# minibotfinal.net
KiCad netlist of a schematic drawn in EAGLE
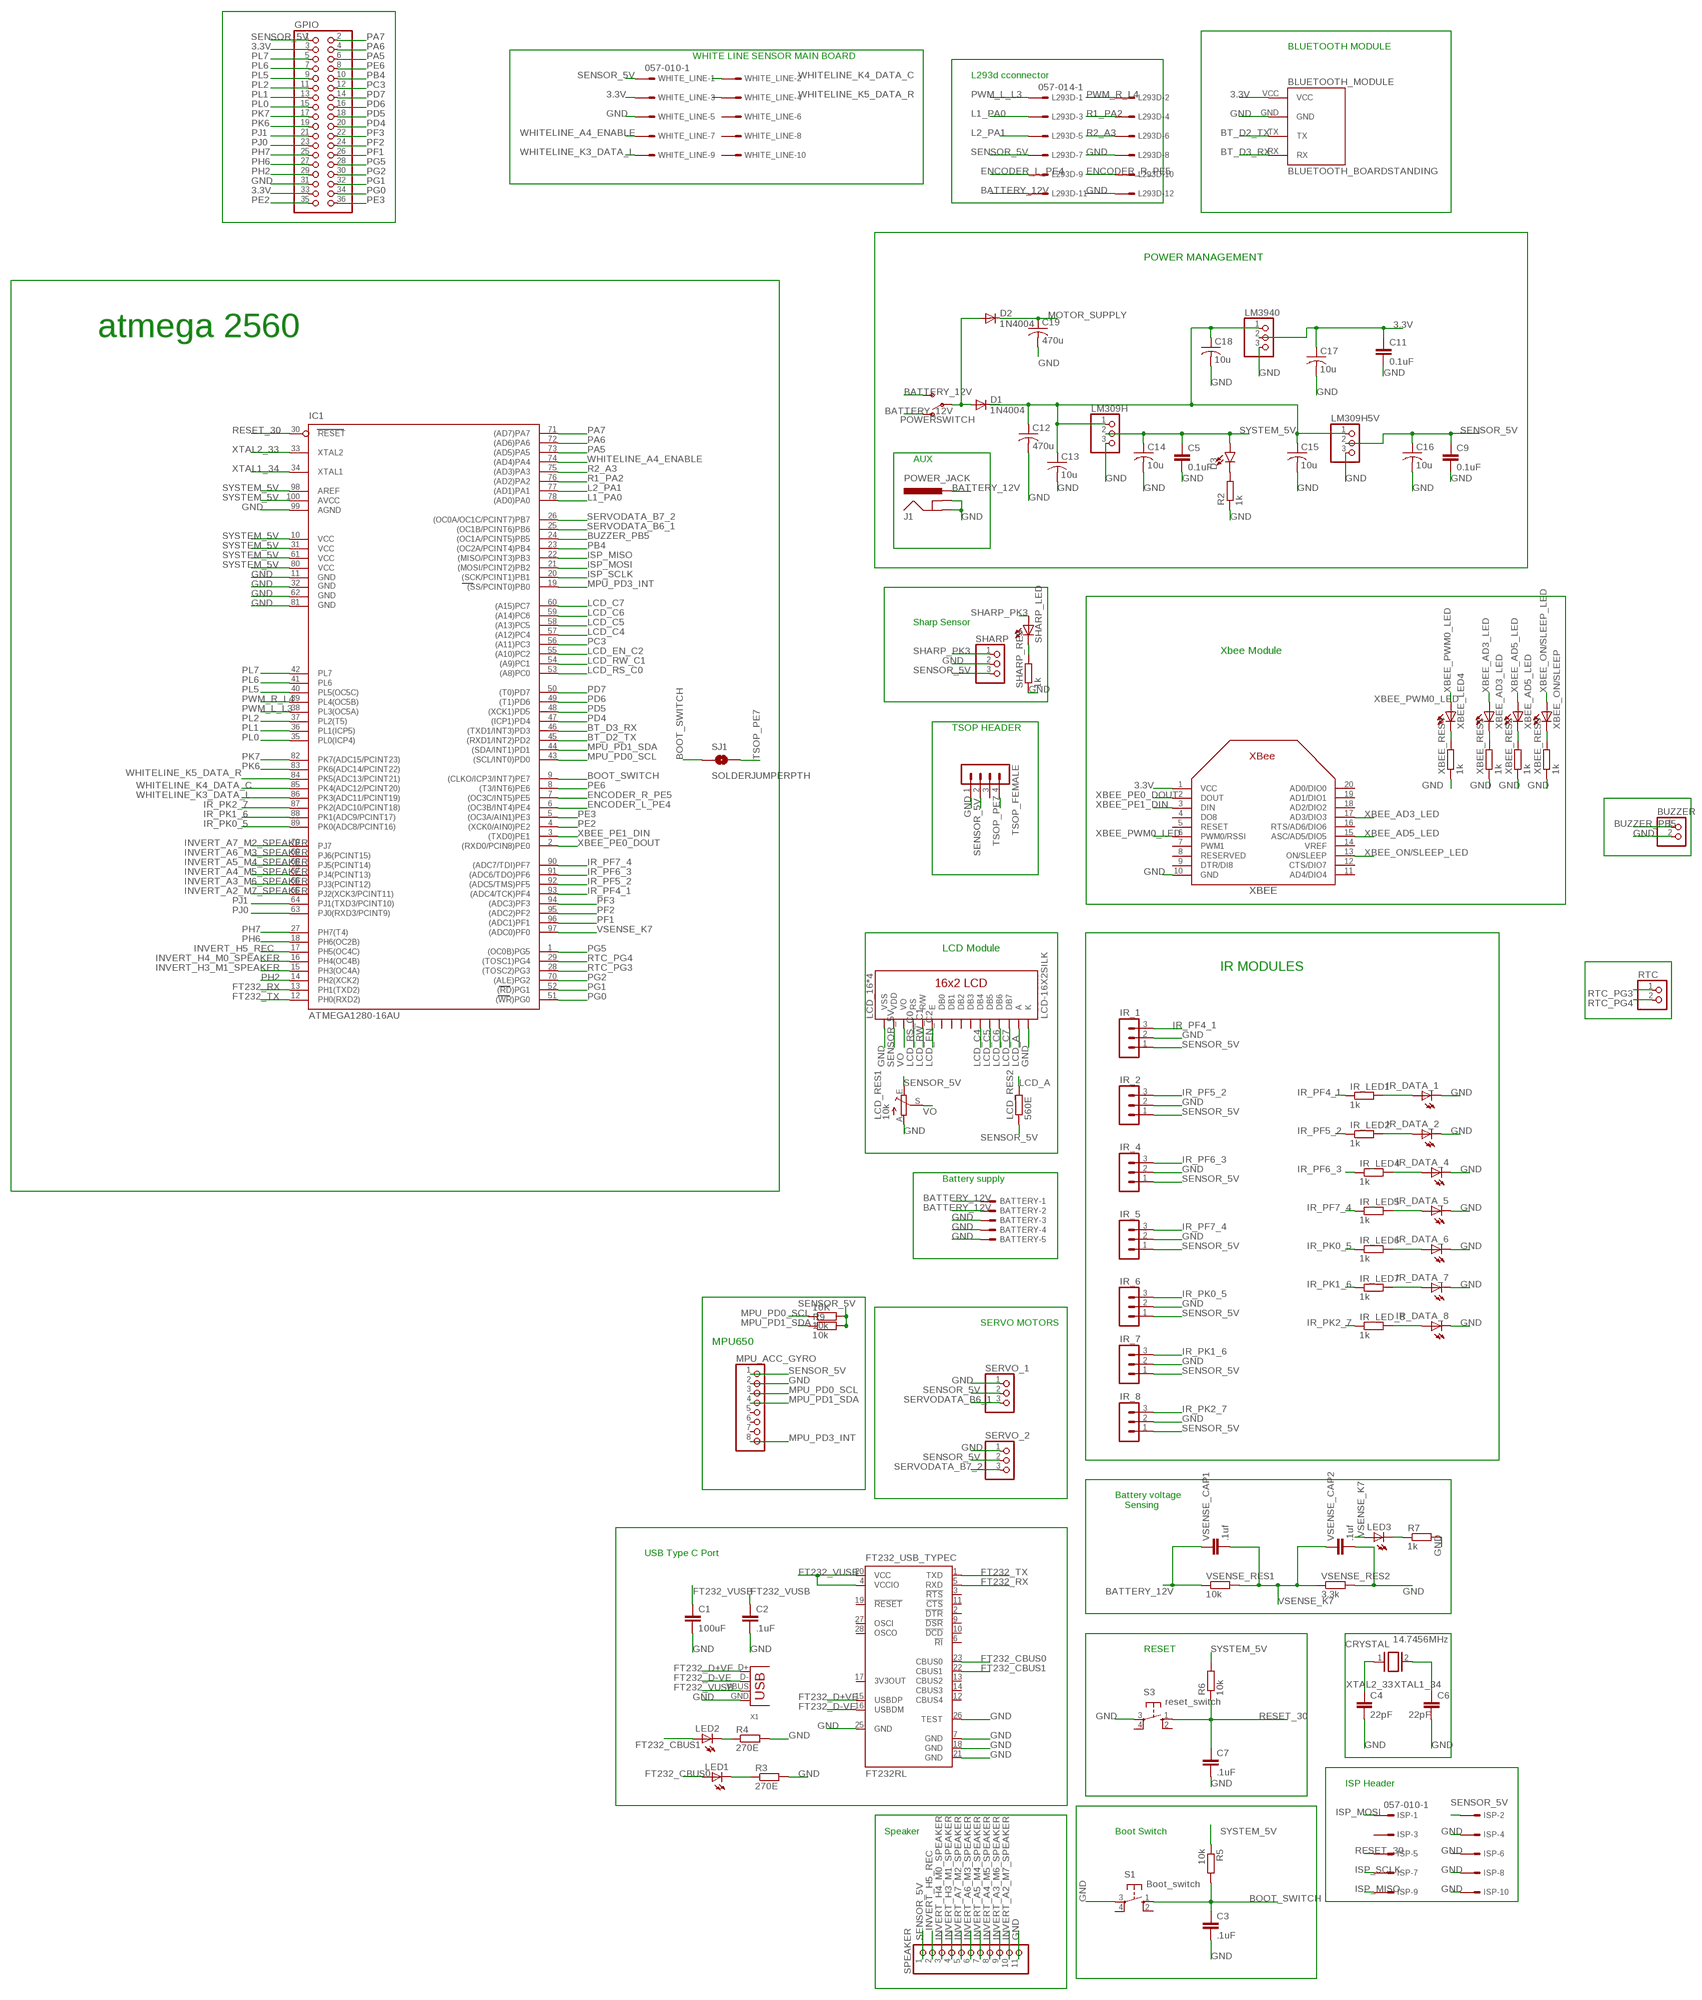
[diagram p0: schematic, sheet 1]

(export (version "E")
  (design (tool "Eeschema 10.0.6"))
  (components
    (comp (ref "10K")
      (value "10k")
      (footprint "eagle-import:R1206")
      (libsource (lib "eagle-import") (part "R-EU_R1206"))
    )
    (comp (ref "BATTERY")
      (value "KK-156-5")
      (footprint "eagle-import:KK-156-5")
      (libsource (lib "eagle-import") (part "KK-156-5"))
    )
    (comp (ref "BLUETOOTH_MODULE")
      (value "BLUETOOTH_BOARDSTANDING")
      (footprint "eagle-import:BT_BOARD_FOOTPRINT_STANDING")
      (libsource (lib "eagle-import") (part "BLUETOOTH_BOARDSTANDING"))
    )
    (comp (ref "BUZZER")
      (value "PINHD-1X2")
      (footprint "eagle-import:1X02")
      (libsource (lib "eagle-import") (part "PINHD-1X2"))
    )
    (comp (ref "C1")
      (value "100uF")
      (footprint "eagle-import:C1206")
      (libsource (lib "eagle-import") (part "C-EUC1206"))
    )
    (comp (ref "C2")
      (value ".1uF")
      (footprint "eagle-import:C1206")
      (libsource (lib "eagle-import") (part "C-EUC1206"))
    )
    (comp (ref "C3")
      (value ".1uF")
      (footprint "eagle-import:C1206")
      (libsource (lib "eagle-import") (part "C-EUC1206"))
    )
    (comp (ref "C4")
      (value "22pF")
      (footprint "eagle-import:C1206")
      (libsource (lib "eagle-import") (part "C-EUC1206"))
    )
    (comp (ref "C5")
      (value "0.1uF")
      (footprint "eagle-import:C1206")
      (libsource (lib "eagle-import") (part "C-EUC1206"))
    )
    (comp (ref "C6")
      (value "22pF")
      (footprint "eagle-import:C1206")
      (libsource (lib "eagle-import") (part "C-EUC1206"))
    )
    (comp (ref "C7")
      (value ".1uF")
      (footprint "eagle-import:C1206")
      (libsource (lib "eagle-import") (part "C-EUC1206"))
    )
    (comp (ref "C9")
      (value "0.1uF")
      (footprint "eagle-import:C1206")
      (libsource (lib "eagle-import") (part "C-EUC1206"))
    )
    (comp (ref "C11")
      (value "0.1uF")
      (footprint "eagle-import:C1206")
      (libsource (lib "eagle-import") (part "C-EUC1206"))
    )
    (comp (ref "C12")
      (value "470u")
      (footprint "eagle-import:C025-050X050")
      (libsource (lib "eagle-import") (part "C-US025-050X050"))
    )
    (comp (ref "C13")
      (value "10u")
      (footprint "eagle-import:C025-050X050")
      (libsource (lib "eagle-import") (part "C-US025-050X050"))
    )
    (comp (ref "C14")
      (value "10u")
      (footprint "eagle-import:C025-050X050")
      (libsource (lib "eagle-import") (part "C-US025-050X050"))
    )
    (comp (ref "C15")
      (value "10u")
      (footprint "eagle-import:C025-050X050")
      (libsource (lib "eagle-import") (part "C-US025-050X050"))
    )
    (comp (ref "C16")
      (value "10u")
      (footprint "eagle-import:C025-050X050")
      (libsource (lib "eagle-import") (part "C-US025-050X050"))
    )
    (comp (ref "C17")
      (value "10u")
      (footprint "eagle-import:C025-050X050")
      (libsource (lib "eagle-import") (part "C-US025-050X050"))
    )
    (comp (ref "C18")
      (value "10u")
      (footprint "eagle-import:C025-050X050")
      (libsource (lib "eagle-import") (part "C-US025-050X050"))
    )
    (comp (ref "C19")
      (value "470u")
      (footprint "eagle-import:C025-050X050")
      (libsource (lib "eagle-import") (part "C-US025-050X050"))
    )
    (comp (ref "CRYSTAL")
      (value "14.7456MHz")
      (footprint "eagle-import:QS")
      (libsource (lib "eagle-import") (part "XTAL/S"))
    )
    (comp (ref "D1")
      (value "1N4004")
      (footprint "eagle-import:DO41-10")
      (libsource (lib "eagle-import") (part "1N4004"))
    )
    (comp (ref "D2")
      (value "1N4004")
      (footprint "eagle-import:DO41-10")
      (libsource (lib "eagle-import") (part "1N4004"))
    )
    (comp (ref "D3")
      (value "LED1206")
      (footprint "eagle-import:LED-1206")
      (libsource (lib "eagle-import") (part "LED1206"))
    )
    (comp (ref "FT232_USB_TYPEC")
      (value "FT232RL")
      (footprint "eagle-import:SSOP28")
      (libsource (lib "eagle-import") (part "FT232RL"))
    )
    (comp (ref "GPIO")
      (value "PINHD-2X18")
      (footprint "eagle-import:2X18")
      (libsource (lib "eagle-import") (part "PINHD-2X18"))
    )
    (comp (ref "IC1")
      (value "ATMEGA1280-16AU")
      (footprint "eagle-import:TQFP100")
      (libsource (lib "eagle-import") (part "ATMEGAAU1280-16"))
    )
    (comp (ref "IR_1")
      (value "MA03-1")
      (footprint "eagle-import:MA03-1")
      (libsource (lib "eagle-import") (part "MA03-1"))
    )
    (comp (ref "IR_2")
      (value "MA03-1")
      (footprint "eagle-import:MA03-1")
      (libsource (lib "eagle-import") (part "MA03-1"))
    )
    (comp (ref "IR_4")
      (value "MA03-1")
      (footprint "eagle-import:MA03-1")
      (libsource (lib "eagle-import") (part "MA03-1"))
    )
    (comp (ref "IR_5")
      (value "MA03-1")
      (footprint "eagle-import:MA03-1")
      (libsource (lib "eagle-import") (part "MA03-1"))
    )
    (comp (ref "IR_6")
      (value "MA03-1")
      (footprint "eagle-import:MA03-1")
      (libsource (lib "eagle-import") (part "MA03-1"))
    )
    (comp (ref "IR_7")
      (value "MA03-1")
      (footprint "eagle-import:MA03-1")
      (libsource (lib "eagle-import") (part "MA03-1"))
    )
    (comp (ref "IR_8")
      (value "MA03-1")
      (footprint "eagle-import:MA03-1")
      (libsource (lib "eagle-import") (part "MA03-1"))
    )
    (comp (ref "IR_DATA_1")
      (value "LEDSMT1206")
      (footprint "eagle-import:1206")
      (libsource (lib "eagle-import") (part "LEDSMT1206"))
    )
    (comp (ref "IR_DATA_2")
      (value "LEDSMT1206")
      (footprint "eagle-import:1206")
      (libsource (lib "eagle-import") (part "LEDSMT1206"))
    )
    (comp (ref "IR_DATA_4")
      (value "LEDSMT1206")
      (footprint "eagle-import:1206")
      (libsource (lib "eagle-import") (part "LEDSMT1206"))
    )
    (comp (ref "IR_DATA_5")
      (value "LEDSMT1206")
      (footprint "eagle-import:1206")
      (libsource (lib "eagle-import") (part "LEDSMT1206"))
    )
    (comp (ref "IR_DATA_6")
      (value "LEDSMT1206")
      (footprint "eagle-import:1206")
      (libsource (lib "eagle-import") (part "LEDSMT1206"))
    )
    (comp (ref "IR_DATA_7")
      (value "LEDSMT1206")
      (footprint "eagle-import:1206")
      (libsource (lib "eagle-import") (part "LEDSMT1206"))
    )
    (comp (ref "IR_DATA_8")
      (value "LEDSMT1206")
      (footprint "eagle-import:1206")
      (libsource (lib "eagle-import") (part "LEDSMT1206"))
    )
    (comp (ref "IR_LED1")
      (value "1k")
      (footprint "eagle-import:R1206")
      (libsource (lib "eagle-import") (part "R-EU_R1206"))
    )
    (comp (ref "IR_LED2")
      (value "1k")
      (footprint "eagle-import:R1206")
      (libsource (lib "eagle-import") (part "R-EU_R1206"))
    )
    (comp (ref "IR_LED4")
      (value "1k")
      (footprint "eagle-import:R1206")
      (libsource (lib "eagle-import") (part "R-EU_R1206"))
    )
    (comp (ref "IR_LED5")
      (value "1k")
      (footprint "eagle-import:R1206")
      (libsource (lib "eagle-import") (part "R-EU_R1206"))
    )
    (comp (ref "IR_LED6")
      (value "1k")
      (footprint "eagle-import:R1206")
      (libsource (lib "eagle-import") (part "R-EU_R1206"))
    )
    (comp (ref "IR_LED7")
      (value "1k")
      (footprint "eagle-import:R1206")
      (libsource (lib "eagle-import") (part "R-EU_R1206"))
    )
    (comp (ref "IR_LED_8")
      (value "1k")
      (footprint "eagle-import:R1206")
      (libsource (lib "eagle-import") (part "R-EU_R1206"))
    )
    (comp (ref "ISP")
      (value "057-010-1")
      (footprint "eagle-import:057-010-1")
      (libsource (lib "eagle-import") (part "057-010-1"))
    )
    (comp (ref "J1")
      (value "POWER_JACK")
      (footprint "eagle-import:POWER_JACK_PTH")
      (libsource (lib "eagle-import") (part "POWER_JACK"))
    )
    (comp (ref "L293D")
      (value "057-014-1")
      (footprint "eagle-import:057-014-1")
      (libsource (lib "eagle-import") (part "057-014-1"))
    )
    (comp (ref "LCD_16*4")
      (value "LCD-16X2SILK")
      (footprint "eagle-import:LCD-16X2")
      (libsource (lib "eagle-import") (part "LCD-16X2SILK"))
    )
    (comp (ref "LCD_RES1")
      (value "10k")
      (footprint "eagle-import:CA6V")
      (libsource (lib "eagle-import") (part "TRIM_EU-CA6V"))
    )
    (comp (ref "LCD_RES2")
      (value "560E")
      (footprint "eagle-import:R1206")
      (libsource (lib "eagle-import") (part "R-EU_R1206"))
    )
    (comp (ref "LED1")
      (value "LEDSMT1206")
      (footprint "eagle-import:1206")
      (libsource (lib "eagle-import") (part "LEDSMT1206"))
    )
    (comp (ref "LED2")
      (value "LEDSMT1206")
      (footprint "eagle-import:1206")
      (libsource (lib "eagle-import") (part "LEDSMT1206"))
    )
    (comp (ref "LED3")
      (value "LEDSMT1206")
      (footprint "eagle-import:1206")
      (libsource (lib "eagle-import") (part "LEDSMT1206"))
    )
    (comp (ref "LM309H")
      (value "PINHD-1X3")
      (footprint "eagle-import:1X03")
      (libsource (lib "eagle-import") (part "PINHD-1X3"))
    )
    (comp (ref "LM309H5V")
      (value "PINHD-1X3")
      (footprint "eagle-import:1X03")
      (libsource (lib "eagle-import") (part "PINHD-1X3"))
    )
    (comp (ref "LM3940")
      (value "PINHD-1X3")
      (footprint "eagle-import:1X03")
      (libsource (lib "eagle-import") (part "PINHD-1X3"))
    )
    (comp (ref "MPU_ACC_GYRO")
      (value "PINHD-1X8")
      (footprint "eagle-import:1X08")
      (libsource (lib "eagle-import") (part "PINHD-1X8"))
    )
    (comp (ref "POWERSWITCH")
      (value "SWITCH-SPDT-PTH-11.6X4.0MM-LOCK")
      (footprint "eagle-import:SWITCH_SPDT_PTH_11.6X4.0MM_LOCK")
      (libsource (lib "eagle-import") (part "SWITCH-SPDT-PTH-11.6X4.0MM-LOCK"))
    )
    (comp (ref "R2")
      (value "1k")
      (footprint "eagle-import:R1206")
      (libsource (lib "eagle-import") (part "R-EU_R1206"))
    )
    (comp (ref "R3")
      (value "270E")
      (footprint "eagle-import:R1206")
      (libsource (lib "eagle-import") (part "R-EU_R1206"))
    )
    (comp (ref "R4")
      (value "270E")
      (footprint "eagle-import:R1206")
      (libsource (lib "eagle-import") (part "R-EU_R1206"))
    )
    (comp (ref "R5")
      (value "10k")
      (footprint "eagle-import:R1206")
      (libsource (lib "eagle-import") (part "R-EU_R1206"))
    )
    (comp (ref "R6")
      (value "10k")
      (footprint "eagle-import:R1206")
      (libsource (lib "eagle-import") (part "R-EU_R1206"))
    )
    (comp (ref "R7")
      (value "1k")
      (footprint "eagle-import:R1206")
      (libsource (lib "eagle-import") (part "R-EU_R1206"))
    )
    (comp (ref "R9")
      (value "10k")
      (footprint "eagle-import:R1206")
      (libsource (lib "eagle-import") (part "R-EU_R1206"))
    )
    (comp (ref "RTC")
      (value "PINHD-1X2")
      (footprint "eagle-import:1X02")
      (libsource (lib "eagle-import") (part "PINHD-1X2"))
    )
    (comp (ref "S1")
      (value "Boot_switch")
      (footprint "eagle-import:B3F-10XX")
      (fields (field (name "MPN") "B3F-1000"))
      (libsource (lib "eagle-import") (part "10-XX"))
    )
    (comp (ref "S3")
      (value "reset_switch")
      (footprint "eagle-import:B3F-10XX")
      (fields (field (name "MPN") "B3F-1000"))
      (libsource (lib "eagle-import") (part "10-XX"))
    )
    (comp (ref "SERVO_1")
      (value "PINHD-1X3")
      (footprint "eagle-import:1X03")
      (libsource (lib "eagle-import") (part "pinhead_325_PINHD-1X3"))
    )
    (comp (ref "SERVO_2")
      (value "PINHD-1X3")
      (footprint "eagle-import:1X03")
      (libsource (lib "eagle-import") (part "pinhead_325_PINHD-1X3"))
    )
    (comp (ref "SHARP")
      (value "PINHD-1X3")
      (footprint "eagle-import:1X03")
      (libsource (lib "eagle-import") (part "pinhead_325_PINHD-1X3"))
    )
    (comp (ref "SHARP_LED")
      (value "LEDSMT1206")
      (footprint "eagle-import:1206")
      (libsource (lib "eagle-import") (part "LEDSMT1206"))
    )
    (comp (ref "SHARP_RES")
      (value "1k")
      (footprint "eagle-import:R1206")
      (libsource (lib "eagle-import") (part "R-EU_R1206"))
    )
    (comp (ref "SJ1")
      (value "SOLDERJUMPERPTH")
      (footprint "eagle-import:SJ_2S-PTH")
      (libsource (lib "eagle-import") (part "SOLDERJUMPERPTH"))
    )
    (comp (ref "SPEAKER")
      (value "PINHD-1X11")
      (footprint "eagle-import:1X11")
      (libsource (lib "eagle-import") (part "PINHD-1X11"))
    )
    (comp (ref "TSOP_FEMALE")
      (value "MA04-1")
      (footprint "eagle-import:MA04-1")
      (libsource (lib "eagle-import") (part "MA04-1"))
    )
    (comp (ref "VSENSE_CAP1")
      (value ".1uf")
      (footprint "eagle-import:C1206")
      (libsource (lib "eagle-import") (part "C-EUC1206"))
    )
    (comp (ref "VSENSE_CAP2")
      (value ".1uf")
      (footprint "eagle-import:C1206")
      (libsource (lib "eagle-import") (part "C-EUC1206"))
    )
    (comp (ref "VSENSE_RES1")
      (value "10k")
      (footprint "eagle-import:R1206")
      (libsource (lib "eagle-import") (part "R-EU_R1206"))
    )
    (comp (ref "VSENSE_RES2")
      (value "3.3k")
      (footprint "eagle-import:R1206")
      (libsource (lib "eagle-import") (part "R-EU_R1206"))
    )
    (comp (ref "WHITE_LINE")
      (value "057-010-1")
      (footprint "eagle-import:057-010-1")
      (libsource (lib "eagle-import") (part "057-010-1"))
    )
    (comp (ref "X1")
      (value "USB-B-H")
      (footprint "eagle-import:USB-B-H")
      (libsource (lib "eagle-import") (part "USB-B-H"))
    )
    (comp (ref "XBEE")
      (value "XBEE")
      (footprint "eagle-import:XBEE")
      (libsource (lib "eagle-import") (part "XBEE"))
    )
    (comp (ref "XBEE_AD3_LED")
      (value "LEDSMT1206")
      (footprint "eagle-import:1206")
      (libsource (lib "eagle-import") (part "LEDSMT1206"))
    )
    (comp (ref "XBEE_AD5_LED")
      (value "LEDSMT1206")
      (footprint "eagle-import:1206")
      (libsource (lib "eagle-import") (part "LEDSMT1206"))
    )
    (comp (ref "XBEE_LED4")
      (value "LEDSMT1206")
      (footprint "eagle-import:1206")
      (libsource (lib "eagle-import") (part "LEDSMT1206"))
    )
    (comp (ref "XBEE_ON/SLEEP")
      (value "LEDSMT1206")
      (footprint "eagle-import:1206")
      (libsource (lib "eagle-import") (part "LEDSMT1206"))
    )
    (comp (ref "XBEE_RES1")
      (value "1k")
      (footprint "eagle-import:M1206")
      (libsource (lib "eagle-import") (part "R-EU_M1206"))
    )
    (comp (ref "XBEE_RES2")
      (value "1k")
      (footprint "eagle-import:M1206")
      (libsource (lib "eagle-import") (part "R-EU_M1206"))
    )
    (comp (ref "XBEE_RES3")
      (value "1k")
      (footprint "eagle-import:M1206")
      (libsource (lib "eagle-import") (part "R-EU_M1206"))
    )
    (comp (ref "XBEE_RES4")
      (value "1k")
      (footprint "eagle-import:M1206")
      (libsource (lib "eagle-import") (part "R-EU_M1206"))
    )
  )
  (nets
    (net (code "1") (name "/3.3V") (class "Default")
      (node (ref "BLUETOOTH_MODULE") (pin "VCC") (pinfunction "VCC_VCC") (pintype "bidirectional"))
      (node (ref "C11") (pin "1") (pinfunction "1_1") (pintype "passive"))
      (node (ref "C17") (pin "1") (pinfunction "1_1") (pintype "passive"))
      (node (ref "GPIO") (pin "3") (pinfunction "3_3") (pintype "passive"))
      (node (ref "GPIO") (pin "33") (pinfunction "33_33") (pintype "passive"))
      (node (ref "LM3940") (pin "2") (pinfunction "2_2") (pintype "passive"))
      (node (ref "WHITE_LINE") (pin "3") (pinfunction "S_3") (pintype "passive"))
      (node (ref "XBEE") (pin "1") (pinfunction "VCC_1") (pintype "power_in"))
    )
    (net (code "2") (name "/BATTERY_12V") (class "Default")
      (node (ref "BATTERY") (pin "1") (pinfunction "S_1") (pintype "passive"))
      (node (ref "BATTERY") (pin "2") (pinfunction "S_2") (pintype "passive"))
      (node (ref "J1") (pin "PWR") (pinfunction "PWR_PWR") (pintype "bidirectional"))
      (node (ref "L293D") (pin "11") (pinfunction "S_11") (pintype "passive"))
      (node (ref "POWERSWITCH") (pin "1") (pinfunction "O_1") (pintype "passive"))
      (node (ref "POWERSWITCH") (pin "3") (pinfunction "S_3") (pintype "passive"))
      (node (ref "VSENSE_CAP1") (pin "1") (pinfunction "1_1") (pintype "passive"))
      (node (ref "VSENSE_RES1") (pin "1") (pinfunction "1_1") (pintype "passive"))
    )
    (net (code "3") (name "/BOOT_SWITCH") (class "Default")
      (node (ref "C3") (pin "1") (pinfunction "1_1") (pintype "passive"))
      (node (ref "IC1") (pin "9") (pinfunction "(CLKO/ICP3/INT7)PE7_9") (pintype "bidirectional"))
      (node (ref "R5") (pin "2") (pinfunction "2_2") (pintype "passive"))
      (node (ref "S1") (pin "1") (pinfunction "S_1") (pintype "passive"))
      (node (ref "SJ1") (pin "1") (pinfunction "1_1") (pintype "passive"))
    )
    (net (code "4") (name "/BT_D2_TX") (class "Default")
      (node (ref "BLUETOOTH_MODULE") (pin "TX") (pinfunction "TX_TX") (pintype "bidirectional"))
      (node (ref "IC1") (pin "45") (pinfunction "(RXD1/INT2)PD2_45") (pintype "bidirectional"))
    )
    (net (code "5") (name "/BT_D3_RX") (class "Default")
      (node (ref "BLUETOOTH_MODULE") (pin "RX") (pinfunction "RX_RX") (pintype "bidirectional"))
      (node (ref "IC1") (pin "46") (pinfunction "(TXD1/INT3)PD3_46") (pintype "bidirectional"))
    )
    (net (code "6") (name "/BUZZER_PB5") (class "Default")
      (node (ref "BUZZER") (pin "1") (pinfunction "1_1") (pintype "passive"))
      (node (ref "IC1") (pin "24") (pinfunction "(OC1A/PCINT5)PB5_24") (pintype "bidirectional"))
    )
    (net (code "7") (name "/ENCODER_L_PE4") (class "Default")
      (node (ref "IC1") (pin "6") (pinfunction "(OC3B/INT4)PE4_6") (pintype "bidirectional"))
      (node (ref "L293D") (pin "9") (pinfunction "S_9") (pintype "passive"))
    )
    (net (code "8") (name "/ENCODER_R_PE5") (class "Default")
      (node (ref "IC1") (pin "7") (pinfunction "(OC3C/INT5)PE5_7") (pintype "bidirectional"))
      (node (ref "L293D") (pin "10") (pinfunction "S_10") (pintype "passive"))
    )
    (net (code "9") (name "/FT232_CBUS0") (class "Default")
      (node (ref "FT232_USB_TYPEC") (pin "23") (pinfunction "CBUS0_23") (pintype "bidirectional"))
      (node (ref "LED1") (pin "A") (pinfunction "A_A") (pintype "passive"))
    )
    (net (code "10") (name "/FT232_CBUS1") (class "Default")
      (node (ref "FT232_USB_TYPEC") (pin "22") (pinfunction "CBUS1_22") (pintype "bidirectional"))
      (node (ref "LED2") (pin "A") (pinfunction "A_A") (pintype "passive"))
    )
    (net (code "11") (name "/FT232_D+VE") (class "Default")
      (node (ref "FT232_USB_TYPEC") (pin "15") (pinfunction "USBDP_15") (pintype "bidirectional"))
      (node (ref "X1") (pin "D+") (pinfunction "D+_D+") (pintype "bidirectional"))
    )
    (net (code "12") (name "/FT232_D-VE") (class "Default")
      (node (ref "FT232_USB_TYPEC") (pin "16") (pinfunction "USBDM_16") (pintype "bidirectional"))
      (node (ref "X1") (pin "D-") (pinfunction "D-_D-") (pintype "bidirectional"))
    )
    (net (code "13") (name "/FT232_RX") (class "Default")
      (node (ref "FT232_USB_TYPEC") (pin "5") (pinfunction "RXD_5") (pintype "input"))
      (node (ref "IC1") (pin "13") (pinfunction "PH1(TXD2)_13") (pintype "bidirectional"))
    )
    (net (code "14") (name "/FT232_TX") (class "Default")
      (node (ref "FT232_USB_TYPEC") (pin "1") (pinfunction "TXD_1") (pintype "output"))
      (node (ref "IC1") (pin "12") (pinfunction "PH0(RXD2)_12") (pintype "bidirectional"))
    )
    (net (code "15") (name "/FT232_VUSB") (class "Default")
      (node (ref "C1") (pin "1") (pinfunction "1_1") (pintype "passive"))
      (node (ref "C2") (pin "1") (pinfunction "1_1") (pintype "passive"))
      (node (ref "FT232_USB_TYPEC") (pin "20") (pinfunction "VCC_20") (pintype "power_in"))
      (node (ref "FT232_USB_TYPEC") (pin "4") (pinfunction "VCCIO_4") (pintype "power_in"))
      (node (ref "X1") (pin "VBUS") (pinfunction "VBUS_VBUS") (pintype "bidirectional"))
    )
    (net (code "16") (name "/GND") (class "Default")
      (node (ref "BATTERY") (pin "3") (pinfunction "S_3") (pintype "passive"))
      (node (ref "BATTERY") (pin "4") (pinfunction "S_4") (pintype "passive"))
      (node (ref "BATTERY") (pin "5") (pinfunction "S_5") (pintype "passive"))
      (node (ref "BLUETOOTH_MODULE") (pin "GND") (pinfunction "GND_GND") (pintype "bidirectional"))
      (node (ref "BUZZER") (pin "2") (pinfunction "2_2") (pintype "passive"))
      (node (ref "C1") (pin "2") (pinfunction "2_2") (pintype "passive"))
      (node (ref "C11") (pin "2") (pinfunction "2_2") (pintype "passive"))
      (node (ref "C12") (pin "2") (pinfunction "2_2") (pintype "passive"))
      (node (ref "C13") (pin "2") (pinfunction "2_2") (pintype "passive"))
      (node (ref "C14") (pin "2") (pinfunction "2_2") (pintype "passive"))
      (node (ref "C15") (pin "2") (pinfunction "2_2") (pintype "passive"))
      (node (ref "C16") (pin "2") (pinfunction "2_2") (pintype "passive"))
      (node (ref "C17") (pin "2") (pinfunction "2_2") (pintype "passive"))
      (node (ref "C18") (pin "2") (pinfunction "2_2") (pintype "passive"))
      (node (ref "C19") (pin "2") (pinfunction "2_2") (pintype "passive"))
      (node (ref "C2") (pin "2") (pinfunction "2_2") (pintype "passive"))
      (node (ref "C3") (pin "2") (pinfunction "2_2") (pintype "passive"))
      (node (ref "C4") (pin "2") (pinfunction "2_2") (pintype "passive"))
      (node (ref "C5") (pin "2") (pinfunction "2_2") (pintype "passive"))
      (node (ref "C6") (pin "2") (pinfunction "2_2") (pintype "passive"))
      (node (ref "C7") (pin "2") (pinfunction "2_2") (pintype "passive"))
      (node (ref "C9") (pin "2") (pinfunction "2_2") (pintype "passive"))
      (node (ref "FT232_USB_TYPEC") (pin "18") (pinfunction "GND_18") (pintype "power_in"))
      (node (ref "FT232_USB_TYPEC") (pin "21") (pinfunction "GND_21") (pintype "power_in"))
      (node (ref "FT232_USB_TYPEC") (pin "25") (pinfunction "GND_25") (pintype "power_in"))
      (node (ref "FT232_USB_TYPEC") (pin "26") (pinfunction "TEST_26") (pintype "input"))
      (node (ref "FT232_USB_TYPEC") (pin "7") (pinfunction "GND_7") (pintype "power_in"))
      (node (ref "GPIO") (pin "31") (pinfunction "31_31") (pintype "passive"))
      (node (ref "IC1") (pin "11") (pinfunction "GND_11") (pintype "power_in"))
      (node (ref "IC1") (pin "32") (pinfunction "GND1_32") (pintype "power_in"))
      (node (ref "IC1") (pin "62") (pinfunction "GND2_62") (pintype "power_in"))
      (node (ref "IC1") (pin "81") (pinfunction "GND3_81") (pintype "power_in"))
      (node (ref "IC1") (pin "99") (pinfunction "AGND_99") (pintype "power_in"))
      (node (ref "IR_1") (pin "2") (pinfunction "2_2") (pintype "passive"))
      (node (ref "IR_2") (pin "2") (pinfunction "2_2") (pintype "passive"))
      (node (ref "IR_4") (pin "2") (pinfunction "2_2") (pintype "passive"))
      (node (ref "IR_5") (pin "2") (pinfunction "2_2") (pintype "passive"))
      (node (ref "IR_6") (pin "2") (pinfunction "2_2") (pintype "passive"))
      (node (ref "IR_7") (pin "2") (pinfunction "2_2") (pintype "passive"))
      (node (ref "IR_8") (pin "2") (pinfunction "2_2") (pintype "passive"))
      (node (ref "IR_DATA_1") (pin "C") (pinfunction "C_C") (pintype "passive"))
      (node (ref "IR_DATA_2") (pin "C") (pinfunction "C_C") (pintype "passive"))
      (node (ref "IR_DATA_4") (pin "C") (pinfunction "C_C") (pintype "passive"))
      (node (ref "IR_DATA_5") (pin "C") (pinfunction "C_C") (pintype "passive"))
      (node (ref "IR_DATA_6") (pin "C") (pinfunction "C_C") (pintype "passive"))
      (node (ref "IR_DATA_7") (pin "C") (pinfunction "C_C") (pintype "passive"))
      (node (ref "IR_DATA_8") (pin "C") (pinfunction "C_C") (pintype "passive"))
      (node (ref "ISP") (pin "10") (pinfunction "S_10") (pintype "passive"))
      (node (ref "ISP") (pin "4") (pinfunction "S_4") (pintype "passive"))
      (node (ref "ISP") (pin "6") (pinfunction "S_6") (pintype "passive"))
      (node (ref "ISP") (pin "8") (pinfunction "S_8") (pintype "passive"))
      (node (ref "J1") (pin "GND") (pinfunction "GND_GND") (pintype "bidirectional"))
      (node (ref "J1") (pin "GNDBREAK") (pinfunction "GNDBREAK_GNDBREAK") (pintype "bidirectional"))
      (node (ref "L293D") (pin "12") (pinfunction "S_12") (pintype "passive"))
      (node (ref "L293D") (pin "8") (pinfunction "S_8") (pintype "passive"))
      (node (ref "LCD_16*4") (pin "1") (pinfunction "VSS_1") (pintype "power_in"))
      (node (ref "LCD_16*4") (pin "16") (pinfunction "K_16") (pintype "power_in"))
      (node (ref "LCD_RES1") (pin "A") (pinfunction "A_A") (pintype "passive"))
      (node (ref "LM309H") (pin "3") (pinfunction "3_3") (pintype "passive"))
      (node (ref "LM309H5V") (pin "3") (pinfunction "3_3") (pintype "passive"))
      (node (ref "LM3940") (pin "3") (pinfunction "3_3") (pintype "passive"))
      (node (ref "MPU_ACC_GYRO") (pin "2") (pinfunction "2_2") (pintype "passive"))
      (node (ref "R2") (pin "1") (pinfunction "1_1") (pintype "passive"))
      (node (ref "R3") (pin "2") (pinfunction "2_2") (pintype "passive"))
      (node (ref "R4") (pin "2") (pinfunction "2_2") (pintype "passive"))
      (node (ref "R7") (pin "2") (pinfunction "2_2") (pintype "passive"))
      (node (ref "S1") (pin "3") (pinfunction "P_3") (pintype "passive"))
      (node (ref "S3") (pin "3") (pinfunction "P_3") (pintype "passive"))
      (node (ref "SERVO_1") (pin "1") (pinfunction "1_1") (pintype "passive"))
      (node (ref "SERVO_2") (pin "1") (pinfunction "1_1") (pintype "passive"))
      (node (ref "SHARP") (pin "2") (pinfunction "2_2") (pintype "passive"))
      (node (ref "SHARP_RES") (pin "1") (pinfunction "1_1") (pintype "passive"))
      (node (ref "SPEAKER") (pin "11") (pinfunction "11_11") (pintype "passive"))
      (node (ref "TSOP_FEMALE") (pin "1") (pinfunction "1_1") (pintype "passive"))
      (node (ref "VSENSE_CAP2") (pin "2") (pinfunction "2_2") (pintype "passive"))
      (node (ref "VSENSE_RES2") (pin "2") (pinfunction "2_2") (pintype "passive"))
      (node (ref "WHITE_LINE") (pin "5") (pinfunction "S_5") (pintype "passive"))
      (node (ref "X1") (pin "GND") (pinfunction "GND_GND") (pintype "bidirectional"))
      (node (ref "XBEE") (pin "10") (pinfunction "GND_10") (pintype "power_in"))
      (node (ref "XBEE_RES1") (pin "1") (pinfunction "1_1") (pintype "passive"))
      (node (ref "XBEE_RES2") (pin "1") (pinfunction "1_1") (pintype "passive"))
      (node (ref "XBEE_RES3") (pin "1") (pinfunction "1_1") (pintype "passive"))
      (node (ref "XBEE_RES4") (pin "1") (pinfunction "1_1") (pintype "passive"))
    )
    (net (code "17") (name "/INVERT_A2_M7_SPEAKER") (class "Default")
      (node (ref "IC1") (pin "65") (pinfunction "PJ2(XCK3/PCINT11)_65") (pintype "bidirectional"))
      (node (ref "SPEAKER") (pin "10") (pinfunction "10_10") (pintype "passive"))
    )
    (net (code "18") (name "/INVERT_A3_M6_SPEAKER") (class "Default")
      (node (ref "IC1") (pin "66") (pinfunction "PJ3(PCINT12)_66") (pintype "bidirectional"))
      (node (ref "SPEAKER") (pin "9") (pinfunction "9_9") (pintype "passive"))
    )
    (net (code "19") (name "/INVERT_A4_M5_SPEAKER") (class "Default")
      (node (ref "IC1") (pin "67") (pinfunction "PJ4(PCINT13)_67") (pintype "bidirectional"))
      (node (ref "SPEAKER") (pin "8") (pinfunction "8_8") (pintype "passive"))
    )
    (net (code "20") (name "/INVERT_A5_M4_SPEAKER") (class "Default")
      (node (ref "IC1") (pin "68") (pinfunction "PJ5(PCINT14)_68") (pintype "bidirectional"))
      (node (ref "SPEAKER") (pin "7") (pinfunction "7_7") (pintype "passive"))
    )
    (net (code "21") (name "/INVERT_A6_M3_SPEAKER") (class "Default")
      (node (ref "IC1") (pin "69") (pinfunction "PJ6(PCINT15)_69") (pintype "bidirectional"))
      (node (ref "SPEAKER") (pin "6") (pinfunction "6_6") (pintype "passive"))
    )
    (net (code "22") (name "/INVERT_A7_M2_SPEAKER") (class "Default")
      (node (ref "IC1") (pin "79") (pinfunction "PJ7_79") (pintype "bidirectional"))
      (node (ref "SPEAKER") (pin "5") (pinfunction "5_5") (pintype "passive"))
    )
    (net (code "23") (name "/INVERT_H3_M1_SPEAKER") (class "Default")
      (node (ref "IC1") (pin "15") (pinfunction "PH3(OC4A)_15") (pintype "bidirectional"))
      (node (ref "SPEAKER") (pin "4") (pinfunction "4_4") (pintype "passive"))
    )
    (net (code "24") (name "/INVERT_H4_M0_SPEAKER") (class "Default")
      (node (ref "IC1") (pin "16") (pinfunction "PH4(OC4B)_16") (pintype "bidirectional"))
      (node (ref "SPEAKER") (pin "3") (pinfunction "3_3") (pintype "passive"))
    )
    (net (code "25") (name "/INVERT_H5_REC") (class "Default")
      (node (ref "IC1") (pin "17") (pinfunction "PH5(OC4C)_17") (pintype "bidirectional"))
      (node (ref "SPEAKER") (pin "2") (pinfunction "2_2") (pintype "passive"))
    )
    (net (code "26") (name "/IR_PF4_1") (class "Default")
      (node (ref "IC1") (pin "93") (pinfunction "(ADC4/TCK)PF4_93") (pintype "bidirectional"))
      (node (ref "IR_1") (pin "3") (pinfunction "3_3") (pintype "passive"))
      (node (ref "IR_LED1") (pin "1") (pinfunction "1_1") (pintype "passive"))
    )
    (net (code "27") (name "/IR_PF5_2") (class "Default")
      (node (ref "IC1") (pin "92") (pinfunction "(ADC5/TMS)PF5_92") (pintype "bidirectional"))
      (node (ref "IR_2") (pin "3") (pinfunction "3_3") (pintype "passive"))
      (node (ref "IR_LED2") (pin "1") (pinfunction "1_1") (pintype "passive"))
    )
    (net (code "28") (name "/IR_PF6_3") (class "Default")
      (node (ref "IC1") (pin "91") (pinfunction "(ADC6/TDO)PF6_91") (pintype "bidirectional"))
      (node (ref "IR_4") (pin "3") (pinfunction "3_3") (pintype "passive"))
      (node (ref "IR_LED4") (pin "1") (pinfunction "1_1") (pintype "passive"))
    )
    (net (code "29") (name "/IR_PF7_4") (class "Default")
      (node (ref "IC1") (pin "90") (pinfunction "(ADC7/TDI)PF7_90") (pintype "bidirectional"))
      (node (ref "IR_5") (pin "3") (pinfunction "3_3") (pintype "passive"))
      (node (ref "IR_LED5") (pin "1") (pinfunction "1_1") (pintype "passive"))
    )
    (net (code "30") (name "/IR_PK0_5") (class "Default")
      (node (ref "IC1") (pin "89") (pinfunction "PK0(ADC8/PCINT16)_89") (pintype "bidirectional"))
      (node (ref "IR_6") (pin "3") (pinfunction "3_3") (pintype "passive"))
      (node (ref "IR_LED6") (pin "1") (pinfunction "1_1") (pintype "passive"))
    )
    (net (code "31") (name "/IR_PK1_6") (class "Default")
      (node (ref "IC1") (pin "88") (pinfunction "PK1(ADC9/PCINT17)_88") (pintype "bidirectional"))
      (node (ref "IR_7") (pin "3") (pinfunction "3_3") (pintype "passive"))
      (node (ref "IR_LED7") (pin "1") (pinfunction "1_1") (pintype "passive"))
    )
    (net (code "32") (name "/IR_PK2_7") (class "Default")
      (node (ref "IC1") (pin "87") (pinfunction "PK2(ADC10/PCINT18)_87") (pintype "bidirectional"))
      (node (ref "IR_8") (pin "3") (pinfunction "3_3") (pintype "passive"))
      (node (ref "IR_LED_8") (pin "1") (pinfunction "1_1") (pintype "passive"))
    )
    (net (code "33") (name "/ISP_MISO") (class "Default")
      (node (ref "IC1") (pin "22") (pinfunction "(MISO/PCINT3)PB3_22") (pintype "bidirectional"))
      (node (ref "ISP") (pin "9") (pinfunction "S_9") (pintype "passive"))
    )
    (net (code "34") (name "/ISP_MOSI") (class "Default")
      (node (ref "IC1") (pin "21") (pinfunction "(MOSI/PCINT2)PB2_21") (pintype "bidirectional"))
      (node (ref "ISP") (pin "1") (pinfunction "S_1") (pintype "passive"))
    )
    (net (code "35") (name "/ISP_SCLK") (class "Default")
      (node (ref "IC1") (pin "20") (pinfunction "(SCK/PCINT1)PB1_20") (pintype "bidirectional"))
      (node (ref "ISP") (pin "7") (pinfunction "S_7") (pintype "passive"))
    )
    (net (code "36") (name "/L1_PA0") (class "Default")
      (node (ref "IC1") (pin "78") (pinfunction "(AD0)PA0_78") (pintype "bidirectional"))
      (node (ref "L293D") (pin "3") (pinfunction "S_3") (pintype "passive"))
    )
    (net (code "37") (name "/L2_PA1") (class "Default")
      (node (ref "IC1") (pin "77") (pinfunction "(AD1)PA1_77") (pintype "bidirectional"))
      (node (ref "L293D") (pin "5") (pinfunction "S_5") (pintype "passive"))
    )
    (net (code "38") (name "/LCD_A") (class "Default")
      (node (ref "LCD_16*4") (pin "15") (pinfunction "A_15") (pintype "power_in"))
      (node (ref "LCD_RES2") (pin "2") (pinfunction "2_2") (pintype "passive"))
    )
    (net (code "39") (name "/LCD_C4") (class "Default")
      (node (ref "IC1") (pin "57") (pinfunction "(A12)PC4_57") (pintype "bidirectional"))
      (node (ref "LCD_16*4") (pin "11") (pinfunction "DB4_11") (pintype "bidirectional"))
    )
    (net (code "40") (name "/LCD_C5") (class "Default")
      (node (ref "IC1") (pin "58") (pinfunction "(A13)PC5_58") (pintype "bidirectional"))
      (node (ref "LCD_16*4") (pin "12") (pinfunction "DB5_12") (pintype "bidirectional"))
    )
    (net (code "41") (name "/LCD_C6") (class "Default")
      (node (ref "IC1") (pin "59") (pinfunction "(A14)PC6_59") (pintype "bidirectional"))
      (node (ref "LCD_16*4") (pin "13") (pinfunction "DB6_13") (pintype "bidirectional"))
    )
    (net (code "42") (name "/LCD_C7") (class "Default")
      (node (ref "IC1") (pin "60") (pinfunction "(A15)PC7_60") (pintype "bidirectional"))
      (node (ref "LCD_16*4") (pin "14") (pinfunction "DB7_14") (pintype "bidirectional"))
    )
    (net (code "43") (name "/LCD_EN_C2") (class "Default")
      (node (ref "IC1") (pin "55") (pinfunction "(A10)PC2_55") (pintype "bidirectional"))
      (node (ref "LCD_16*4") (pin "6") (pinfunction "E_6") (pintype "input"))
    )
    (net (code "44") (name "/LCD_RS_C0") (class "Default")
      (node (ref "IC1") (pin "53") (pinfunction "(A8)PC0_53") (pintype "bidirectional"))
      (node (ref "LCD_16*4") (pin "4") (pinfunction "RS_4") (pintype "input"))
    )
    (net (code "45") (name "/LCD_RW_C1") (class "Default")
      (node (ref "IC1") (pin "54") (pinfunction "(A9)PC1_54") (pintype "bidirectional"))
      (node (ref "LCD_16*4") (pin "5") (pinfunction "R/W_5") (pintype "input"))
    )
    (net (code "46") (name "/MOTOR_SUPPLY") (class "Default")
      (node (ref "C19") (pin "1") (pinfunction "1_1") (pintype "passive"))
      (node (ref "D2") (pin "C") (pinfunction "C_C") (pintype "passive"))
    )
    (net (code "47") (name "/MPU_PD0_SCL") (class "Default")
      (node (ref "10K") (pin "1") (pinfunction "1_1") (pintype "passive"))
      (node (ref "IC1") (pin "43") (pinfunction "(SCL/INT0)PD0_43") (pintype "bidirectional"))
      (node (ref "MPU_ACC_GYRO") (pin "3") (pinfunction "3_3") (pintype "passive"))
    )
    (net (code "48") (name "/MPU_PD1_SDA") (class "Default")
      (node (ref "IC1") (pin "44") (pinfunction "(SDA/INT1)PD1_44") (pintype "bidirectional"))
      (node (ref "MPU_ACC_GYRO") (pin "4") (pinfunction "4_4") (pintype "passive"))
      (node (ref "R9") (pin "1") (pinfunction "1_1") (pintype "passive"))
    )
    (net (code "49") (name "/MPU_PD3_INT") (class "Default")
      (node (ref "IC1") (pin "19") (pinfunction "(SS/PCINT0)PB0_19") (pintype "bidirectional"))
      (node (ref "MPU_ACC_GYRO") (pin "8") (pinfunction "8_8") (pintype "passive"))
    )
    (net (code "50") (name "/PA5") (class "Default")
      (node (ref "GPIO") (pin "6") (pinfunction "6_6") (pintype "passive"))
      (node (ref "IC1") (pin "73") (pinfunction "(AD5)PA5_73") (pintype "bidirectional"))
    )
    (net (code "51") (name "/PA6") (class "Default")
      (node (ref "GPIO") (pin "4") (pinfunction "4_4") (pintype "passive"))
      (node (ref "IC1") (pin "72") (pinfunction "(AD6)PA6_72") (pintype "bidirectional"))
    )
    (net (code "52") (name "/PA7") (class "Default")
      (node (ref "GPIO") (pin "2") (pinfunction "2_2") (pintype "passive"))
      (node (ref "IC1") (pin "71") (pinfunction "(AD7)PA7_71") (pintype "bidirectional"))
    )
    (net (code "53") (name "/PB4") (class "Default")
      (node (ref "GPIO") (pin "10") (pinfunction "10_10") (pintype "passive"))
      (node (ref "IC1") (pin "23") (pinfunction "(OC2A/PCINT4)PB4_23") (pintype "bidirectional"))
    )
    (net (code "54") (name "/PC3") (class "Default")
      (node (ref "GPIO") (pin "12") (pinfunction "12_12") (pintype "passive"))
      (node (ref "IC1") (pin "56") (pinfunction "(A11)PC3_56") (pintype "bidirectional"))
    )
    (net (code "55") (name "/PD4") (class "Default")
      (node (ref "GPIO") (pin "20") (pinfunction "20_20") (pintype "passive"))
      (node (ref "IC1") (pin "47") (pinfunction "(ICP1)PD4_47") (pintype "bidirectional"))
    )
    (net (code "56") (name "/PD5") (class "Default")
      (node (ref "GPIO") (pin "18") (pinfunction "18_18") (pintype "passive"))
      (node (ref "IC1") (pin "48") (pinfunction "(XCK1)PD5_48") (pintype "bidirectional"))
    )
    (net (code "57") (name "/PD6") (class "Default")
      (node (ref "GPIO") (pin "16") (pinfunction "16_16") (pintype "passive"))
      (node (ref "IC1") (pin "49") (pinfunction "(T1)PD6_49") (pintype "bidirectional"))
    )
    (net (code "58") (name "/PD7") (class "Default")
      (node (ref "GPIO") (pin "14") (pinfunction "14_14") (pintype "passive"))
      (node (ref "IC1") (pin "50") (pinfunction "(T0)PD7_50") (pintype "bidirectional"))
    )
    (net (code "59") (name "/PE2") (class "Default")
      (node (ref "GPIO") (pin "35") (pinfunction "35_35") (pintype "passive"))
      (node (ref "IC1") (pin "4") (pinfunction "(XCK0/AIN0)PE2_4") (pintype "bidirectional"))
    )
    (net (code "60") (name "/PE3") (class "Default")
      (node (ref "GPIO") (pin "36") (pinfunction "36_36") (pintype "passive"))
      (node (ref "IC1") (pin "5") (pinfunction "(OC3A/AIN1)PE3_5") (pintype "bidirectional"))
    )
    (net (code "61") (name "/PE6") (class "Default")
      (node (ref "GPIO") (pin "8") (pinfunction "8_8") (pintype "passive"))
      (node (ref "IC1") (pin "8") (pinfunction "(T3/INT6)PE6_8") (pintype "bidirectional"))
    )
    (net (code "62") (name "/PF1") (class "Default")
      (node (ref "GPIO") (pin "26") (pinfunction "26_26") (pintype "passive"))
      (node (ref "IC1") (pin "96") (pinfunction "(ADC1)PF1_96") (pintype "bidirectional"))
    )
    (net (code "63") (name "/PF2") (class "Default")
      (node (ref "GPIO") (pin "24") (pinfunction "24_24") (pintype "passive"))
      (node (ref "IC1") (pin "95") (pinfunction "(ADC2)PF2_95") (pintype "bidirectional"))
    )
    (net (code "64") (name "/PF3") (class "Default")
      (node (ref "GPIO") (pin "22") (pinfunction "22_22") (pintype "passive"))
      (node (ref "IC1") (pin "94") (pinfunction "(ADC3)PF3_94") (pintype "bidirectional"))
    )
    (net (code "65") (name "/PG0") (class "Default")
      (node (ref "GPIO") (pin "34") (pinfunction "34_34") (pintype "passive"))
      (node (ref "IC1") (pin "51") (pinfunction "(WR)PG0_51") (pintype "bidirectional"))
    )
    (net (code "66") (name "/PG1") (class "Default")
      (node (ref "GPIO") (pin "32") (pinfunction "32_32") (pintype "passive"))
      (node (ref "IC1") (pin "52") (pinfunction "(RD)PG1_52") (pintype "bidirectional"))
    )
    (net (code "67") (name "/PG2") (class "Default")
      (node (ref "GPIO") (pin "30") (pinfunction "30_30") (pintype "passive"))
      (node (ref "IC1") (pin "70") (pinfunction "(ALE)PG2_70") (pintype "bidirectional"))
    )
    (net (code "68") (name "/PG5") (class "Default")
      (node (ref "GPIO") (pin "28") (pinfunction "28_28") (pintype "passive"))
      (node (ref "IC1") (pin "1") (pinfunction "(OC0B)PG5_1") (pintype "bidirectional"))
    )
    (net (code "69") (name "/PH2") (class "Default")
      (node (ref "GPIO") (pin "29") (pinfunction "29_29") (pintype "passive"))
      (node (ref "IC1") (pin "14") (pinfunction "PH2(XCK2)_14") (pintype "bidirectional"))
    )
    (net (code "70") (name "/PH6") (class "Default")
      (node (ref "GPIO") (pin "27") (pinfunction "27_27") (pintype "passive"))
      (node (ref "IC1") (pin "18") (pinfunction "PH6(OC2B)_18") (pintype "bidirectional"))
    )
    (net (code "71") (name "/PH7") (class "Default")
      (node (ref "GPIO") (pin "25") (pinfunction "25_25") (pintype "passive"))
      (node (ref "IC1") (pin "27") (pinfunction "PH7(T4)_27") (pintype "bidirectional"))
    )
    (net (code "72") (name "/PJ0") (class "Default")
      (node (ref "GPIO") (pin "23") (pinfunction "23_23") (pintype "passive"))
      (node (ref "IC1") (pin "63") (pinfunction "PJ0(RXD3/PCINT9)_63") (pintype "bidirectional"))
    )
    (net (code "73") (name "/PJ1") (class "Default")
      (node (ref "GPIO") (pin "21") (pinfunction "21_21") (pintype "passive"))
      (node (ref "IC1") (pin "64") (pinfunction "PJ1(TXD3/PCINT10)_64") (pintype "bidirectional"))
    )
    (net (code "74") (name "/PK6") (class "Default")
      (node (ref "GPIO") (pin "19") (pinfunction "19_19") (pintype "passive"))
      (node (ref "IC1") (pin "83") (pinfunction "PK6(ADC14/PCINT22)_83") (pintype "bidirectional"))
    )
    (net (code "75") (name "/PK7") (class "Default")
      (node (ref "GPIO") (pin "17") (pinfunction "17_17") (pintype "passive"))
      (node (ref "IC1") (pin "82") (pinfunction "PK7(ADC15/PCINT23)_82") (pintype "bidirectional"))
    )
    (net (code "76") (name "/PL0") (class "Default")
      (node (ref "GPIO") (pin "15") (pinfunction "15_15") (pintype "passive"))
      (node (ref "IC1") (pin "35") (pinfunction "PL0(ICP4)_35") (pintype "bidirectional"))
    )
    (net (code "77") (name "/PL1") (class "Default")
      (node (ref "GPIO") (pin "13") (pinfunction "13_13") (pintype "passive"))
      (node (ref "IC1") (pin "36") (pinfunction "PL1(ICP5)_36") (pintype "bidirectional"))
    )
    (net (code "78") (name "/PL2") (class "Default")
      (node (ref "GPIO") (pin "11") (pinfunction "11_11") (pintype "passive"))
      (node (ref "IC1") (pin "37") (pinfunction "PL2(T5)_37") (pintype "bidirectional"))
    )
    (net (code "79") (name "/PL5") (class "Default")
      (node (ref "GPIO") (pin "9") (pinfunction "9_9") (pintype "passive"))
      (node (ref "IC1") (pin "40") (pinfunction "PL5(OC5C)_40") (pintype "bidirectional"))
    )
    (net (code "80") (name "/PL6") (class "Default")
      (node (ref "GPIO") (pin "7") (pinfunction "7_7") (pintype "passive"))
      (node (ref "IC1") (pin "41") (pinfunction "PL6_41") (pintype "bidirectional"))
    )
    (net (code "81") (name "/PL7") (class "Default")
      (node (ref "GPIO") (pin "5") (pinfunction "5_5") (pintype "passive"))
      (node (ref "IC1") (pin "42") (pinfunction "PL7_42") (pintype "bidirectional"))
    )
    (net (code "82") (name "/PWM_L_L3") (class "Default")
      (node (ref "IC1") (pin "38") (pinfunction "PL3(OC5A)_38") (pintype "bidirectional"))
      (node (ref "L293D") (pin "1") (pinfunction "S_1") (pintype "passive"))
    )
    (net (code "83") (name "/PWM_R_L4") (class "Default")
      (node (ref "IC1") (pin "39") (pinfunction "PL4(OC5B)_39") (pintype "bidirectional"))
      (node (ref "L293D") (pin "2") (pinfunction "S_2") (pintype "passive"))
    )
    (net (code "84") (name "/R1_PA2") (class "Default")
      (node (ref "IC1") (pin "76") (pinfunction "(AD2)PA2_76") (pintype "bidirectional"))
      (node (ref "L293D") (pin "4") (pinfunction "S_4") (pintype "passive"))
    )
    (net (code "85") (name "/R2_A3") (class "Default")
      (node (ref "IC1") (pin "75") (pinfunction "(AD3)PA3_75") (pintype "bidirectional"))
      (node (ref "L293D") (pin "6") (pinfunction "S_6") (pintype "passive"))
    )
    (net (code "86") (name "/RESET_30") (class "Default")
      (node (ref "C7") (pin "1") (pinfunction "1_1") (pintype "passive"))
      (node (ref "IC1") (pin "30") (pinfunction "RESET_30") (pintype "input"))
      (node (ref "ISP") (pin "5") (pinfunction "S_5") (pintype "passive"))
      (node (ref "R6") (pin "1") (pinfunction "1_1") (pintype "passive"))
      (node (ref "S3") (pin "1") (pinfunction "S_1") (pintype "passive"))
    )
    (net (code "87") (name "/RTC_PG3") (class "Default")
      (node (ref "IC1") (pin "28") (pinfunction "(TOSC2)PG3_28") (pintype "bidirectional"))
      (node (ref "RTC") (pin "1") (pinfunction "1_1") (pintype "passive"))
    )
    (net (code "88") (name "/RTC_PG4") (class "Default")
      (node (ref "IC1") (pin "29") (pinfunction "(TOSC1)PG4_29") (pintype "bidirectional"))
      (node (ref "RTC") (pin "2") (pinfunction "2_2") (pintype "passive"))
    )
    (net (code "89") (name "/SENSOR_5V") (class "Default")
      (node (ref "10K") (pin "2") (pinfunction "2_2") (pintype "passive"))
      (node (ref "C16") (pin "1") (pinfunction "1_1") (pintype "passive"))
      (node (ref "C9") (pin "1") (pinfunction "1_1") (pintype "passive"))
      (node (ref "GPIO") (pin "1") (pinfunction "1_1") (pintype "passive"))
      (node (ref "IR_1") (pin "1") (pinfunction "1_1") (pintype "passive"))
      (node (ref "IR_2") (pin "1") (pinfunction "1_1") (pintype "passive"))
      (node (ref "IR_4") (pin "1") (pinfunction "1_1") (pintype "passive"))
      (node (ref "IR_5") (pin "1") (pinfunction "1_1") (pintype "passive"))
      (node (ref "IR_6") (pin "1") (pinfunction "1_1") (pintype "passive"))
      (node (ref "IR_7") (pin "1") (pinfunction "1_1") (pintype "passive"))
      (node (ref "IR_8") (pin "1") (pinfunction "1_1") (pintype "passive"))
      (node (ref "ISP") (pin "2") (pinfunction "S_2") (pintype "passive"))
      (node (ref "L293D") (pin "7") (pinfunction "S_7") (pintype "passive"))
      (node (ref "LCD_16*4") (pin "2") (pinfunction "VDD_2") (pintype "power_in"))
      (node (ref "LCD_RES1") (pin "E") (pinfunction "E_E") (pintype "passive"))
      (node (ref "LCD_RES2") (pin "1") (pinfunction "1_1") (pintype "passive"))
      (node (ref "LM309H5V") (pin "2") (pinfunction "2_2") (pintype "passive"))
      (node (ref "MPU_ACC_GYRO") (pin "1") (pinfunction "1_1") (pintype "passive"))
      (node (ref "R9") (pin "2") (pinfunction "2_2") (pintype "passive"))
      (node (ref "SERVO_1") (pin "2") (pinfunction "2_2") (pintype "passive"))
      (node (ref "SERVO_2") (pin "2") (pinfunction "2_2") (pintype "passive"))
      (node (ref "SHARP") (pin "3") (pinfunction "3_3") (pintype "passive"))
      (node (ref "SPEAKER") (pin "1") (pinfunction "1_1") (pintype "passive"))
      (node (ref "TSOP_FEMALE") (pin "2") (pinfunction "2_2") (pintype "passive"))
      (node (ref "WHITE_LINE") (pin "1") (pinfunction "S_1") (pintype "passive"))
    )
    (net (code "90") (name "/SERVODATA_B6_1") (class "Default")
      (node (ref "IC1") (pin "25") (pinfunction "(OC1B/PCINT6)PB6_25") (pintype "bidirectional"))
      (node (ref "SERVO_1") (pin "3") (pinfunction "3_3") (pintype "passive"))
    )
    (net (code "91") (name "/SERVODATA_B7_2") (class "Default")
      (node (ref "IC1") (pin "26") (pinfunction "(OC0A/OC1C/PCINT7)PB7_26") (pintype "bidirectional"))
      (node (ref "SERVO_2") (pin "3") (pinfunction "3_3") (pintype "passive"))
    )
    (net (code "92") (name "/SHARP_PK3") (class "Default")
      (node (ref "SHARP") (pin "1") (pinfunction "1_1") (pintype "passive"))
      (node (ref "SHARP_LED") (pin "A") (pinfunction "A_A") (pintype "passive"))
    )
    (net (code "93") (name "/SYSTEM_5V") (class "Default")
      (node (ref "C14") (pin "1") (pinfunction "1_1") (pintype "passive"))
      (node (ref "C5") (pin "1") (pinfunction "1_1") (pintype "passive"))
      (node (ref "D3") (pin "A") (pinfunction "A_A") (pintype "passive"))
      (node (ref "IC1") (pin "10") (pinfunction "VCC_10") (pintype "power_in"))
      (node (ref "IC1") (pin "100") (pinfunction "AVCC_100") (pintype "power_in"))
      (node (ref "IC1") (pin "31") (pinfunction "VCC1_31") (pintype "power_in"))
      (node (ref "IC1") (pin "61") (pinfunction "VCC2_61") (pintype "power_in"))
      (node (ref "IC1") (pin "80") (pinfunction "VCC3_80") (pintype "power_in"))
      (node (ref "IC1") (pin "98") (pinfunction "AREF_98") (pintype "bidirectional"))
      (node (ref "LM309H") (pin "2") (pinfunction "2_2") (pintype "passive"))
      (node (ref "R5") (pin "1") (pinfunction "1_1") (pintype "passive"))
      (node (ref "R6") (pin "2") (pinfunction "2_2") (pintype "passive"))
    )
    (net (code "94") (name "/TSOP_PE7") (class "Default")
      (node (ref "SJ1") (pin "2") (pinfunction "2_2") (pintype "passive"))
      (node (ref "TSOP_FEMALE") (pin "4") (pinfunction "4_4") (pintype "passive"))
    )
    (net (code "95") (name "/VO") (class "Default")
      (node (ref "LCD_16*4") (pin "3") (pinfunction "VO_3") (pintype "bidirectional"))
      (node (ref "LCD_RES1") (pin "S") (pinfunction "S_S") (pintype "passive"))
    )
    (net (code "96") (name "/VSENSE_K7") (class "Default")
      (node (ref "IC1") (pin "97") (pinfunction "(ADC0)PF0_97") (pintype "bidirectional"))
      (node (ref "LED3") (pin "A") (pinfunction "A_A") (pintype "passive"))
      (node (ref "VSENSE_CAP1") (pin "2") (pinfunction "2_2") (pintype "passive"))
      (node (ref "VSENSE_CAP2") (pin "1") (pinfunction "1_1") (pintype "passive"))
      (node (ref "VSENSE_RES1") (pin "2") (pinfunction "2_2") (pintype "passive"))
      (node (ref "VSENSE_RES2") (pin "1") (pinfunction "1_1") (pintype "passive"))
    )
    (net (code "97") (name "/WHITELINE_A4_ENABLE") (class "Default")
      (node (ref "IC1") (pin "74") (pinfunction "(AD4)PA4_74") (pintype "bidirectional"))
      (node (ref "WHITE_LINE") (pin "7") (pinfunction "S_7") (pintype "passive"))
    )
    (net (code "98") (name "/WHITELINE_K3_DATA_L") (class "Default")
      (node (ref "IC1") (pin "86") (pinfunction "PK3(ADC11/PCINT19)_86") (pintype "bidirectional"))
      (node (ref "WHITE_LINE") (pin "9") (pinfunction "S_9") (pintype "passive"))
    )
    (net (code "99") (name "/WHITELINE_K4_DATA_C") (class "Default")
      (node (ref "IC1") (pin "85") (pinfunction "PK4(ADC12/PCINT20)_85") (pintype "bidirectional"))
      (node (ref "WHITE_LINE") (pin "2") (pinfunction "S_2") (pintype "passive"))
    )
    (net (code "100") (name "/WHITELINE_K5_DATA_R") (class "Default")
      (node (ref "IC1") (pin "84") (pinfunction "PK5(ADC13/PCINT21)_84") (pintype "bidirectional"))
      (node (ref "WHITE_LINE") (pin "4") (pinfunction "S_4") (pintype "passive"))
    )
    (net (code "101") (name "/XBEE_AD3_LED") (class "Default")
      (node (ref "XBEE") (pin "17") (pinfunction "AD3/DIO3_17") (pintype "bidirectional"))
      (node (ref "XBEE_AD3_LED") (pin "A") (pinfunction "A_A") (pintype "passive"))
    )
    (net (code "102") (name "/XBEE_AD5_LED") (class "Default")
      (node (ref "XBEE") (pin "15") (pinfunction "ASC/AD5/DIO5_15") (pintype "bidirectional"))
      (node (ref "XBEE_AD5_LED") (pin "A") (pinfunction "A_A") (pintype "passive"))
    )
    (net (code "103") (name "/XBEE_ON{slash}SLEEP_LED") (class "Default")
      (node (ref "XBEE") (pin "13") (pinfunction "ON/SLEEP_13") (pintype "output"))
      (node (ref "XBEE_ON/SLEEP") (pin "A") (pinfunction "A_A") (pintype "passive"))
    )
    (net (code "104") (name "/XBEE_PE0_DOUT") (class "Default")
      (node (ref "IC1") (pin "2") (pinfunction "(RXD0/PCIN8)PE0_2") (pintype "bidirectional"))
      (node (ref "XBEE") (pin "2") (pinfunction "DOUT_2") (pintype "output"))
    )
    (net (code "105") (name "/XBEE_PE1_DIN") (class "Default")
      (node (ref "IC1") (pin "3") (pinfunction "(TXD0)PE1_3") (pintype "bidirectional"))
      (node (ref "XBEE") (pin "3") (pinfunction "DIN_3") (pintype "input"))
    )
    (net (code "106") (name "/XBEE_PWM0_LED") (class "Default")
      (node (ref "XBEE") (pin "6") (pinfunction "PWM0/RSSI_6") (pintype "output"))
      (node (ref "XBEE_LED4") (pin "A") (pinfunction "A_A") (pintype "passive"))
    )
    (net (code "107") (name "/XTAL1_34") (class "Default")
      (node (ref "C6") (pin "1") (pinfunction "1_1") (pintype "passive"))
      (node (ref "CRYSTAL") (pin "2") (pinfunction "2_2") (pintype "passive"))
      (node (ref "IC1") (pin "34") (pinfunction "XTAL1_34") (pintype "input"))
    )
    (net (code "108") (name "/XTAL2_33") (class "Default")
      (node (ref "C4") (pin "1") (pinfunction "1_1") (pintype "passive"))
      (node (ref "CRYSTAL") (pin "1") (pinfunction "1_1") (pintype "passive"))
      (node (ref "IC1") (pin "33") (pinfunction "XTAL2_33") (pintype "output"))
    )
    (net (code "109") (name "Net-(C12-Pad1)") (class "Default")
      (node (ref "C12") (pin "1") (pinfunction "1_1") (pintype "passive"))
      (node (ref "C13") (pin "1") (pinfunction "1_1") (pintype "passive"))
      (node (ref "C15") (pin "1") (pinfunction "1_1") (pintype "passive"))
      (node (ref "C18") (pin "1") (pinfunction "1_1") (pintype "passive"))
      (node (ref "D1") (pin "C") (pinfunction "C_C") (pintype "passive"))
      (node (ref "LM309H") (pin "1") (pinfunction "1_1") (pintype "passive"))
      (node (ref "LM309H5V") (pin "1") (pinfunction "1_1") (pintype "passive"))
      (node (ref "LM3940") (pin "1") (pinfunction "1_1") (pintype "passive"))
    )
    (net (code "110") (name "Net-(D3-PadC)") (class "Default")
      (node (ref "D3") (pin "C") (pinfunction "C_C") (pintype "passive"))
      (node (ref "R2") (pin "2") (pinfunction "2_2") (pintype "passive"))
    )
    (net (code "111") (name "Net-(IR_DATA_1-PadA)") (class "Default")
      (node (ref "IR_DATA_1") (pin "A") (pinfunction "A_A") (pintype "passive"))
      (node (ref "IR_LED1") (pin "2") (pinfunction "2_2") (pintype "passive"))
    )
    (net (code "112") (name "Net-(IR_DATA_2-PadA)") (class "Default")
      (node (ref "IR_DATA_2") (pin "A") (pinfunction "A_A") (pintype "passive"))
      (node (ref "IR_LED2") (pin "2") (pinfunction "2_2") (pintype "passive"))
    )
    (net (code "113") (name "Net-(IR_DATA_4-PadA)") (class "Default")
      (node (ref "IR_DATA_4") (pin "A") (pinfunction "A_A") (pintype "passive"))
      (node (ref "IR_LED4") (pin "2") (pinfunction "2_2") (pintype "passive"))
    )
    (net (code "114") (name "Net-(IR_DATA_5-PadA)") (class "Default")
      (node (ref "IR_DATA_5") (pin "A") (pinfunction "A_A") (pintype "passive"))
      (node (ref "IR_LED5") (pin "2") (pinfunction "2_2") (pintype "passive"))
    )
    (net (code "115") (name "Net-(IR_DATA_6-PadA)") (class "Default")
      (node (ref "IR_DATA_6") (pin "A") (pinfunction "A_A") (pintype "passive"))
      (node (ref "IR_LED6") (pin "2") (pinfunction "2_2") (pintype "passive"))
    )
    (net (code "116") (name "Net-(IR_DATA_7-PadA)") (class "Default")
      (node (ref "IR_DATA_7") (pin "A") (pinfunction "A_A") (pintype "passive"))
      (node (ref "IR_LED7") (pin "2") (pinfunction "2_2") (pintype "passive"))
    )
    (net (code "117") (name "Net-(IR_DATA_8-PadA)") (class "Default")
      (node (ref "IR_DATA_8") (pin "A") (pinfunction "A_A") (pintype "passive"))
      (node (ref "IR_LED_8") (pin "2") (pinfunction "2_2") (pintype "passive"))
    )
    (net (code "118") (name "Net-(LED1-PadC)") (class "Default")
      (node (ref "LED1") (pin "C") (pinfunction "C_C") (pintype "passive"))
      (node (ref "R3") (pin "1") (pinfunction "1_1") (pintype "passive"))
    )
    (net (code "119") (name "Net-(LED2-PadC)") (class "Default")
      (node (ref "LED2") (pin "C") (pinfunction "C_C") (pintype "passive"))
      (node (ref "R4") (pin "1") (pinfunction "1_1") (pintype "passive"))
    )
    (net (code "120") (name "Net-(LED3-PadC)") (class "Default")
      (node (ref "LED3") (pin "C") (pinfunction "C_C") (pintype "passive"))
      (node (ref "R7") (pin "1") (pinfunction "1_1") (pintype "passive"))
    )
    (net (code "121") (name "Net-(POWERSWITCH-P)") (class "Default")
      (node (ref "D1") (pin "A") (pinfunction "A_A") (pintype "passive"))
      (node (ref "D2") (pin "A") (pinfunction "A_A") (pintype "passive"))
      (node (ref "POWERSWITCH") (pin "2") (pinfunction "P_2") (pintype "passive"))
    )
    (net (code "122") (name "Net-(SHARP_LED-PadC)") (class "Default")
      (node (ref "SHARP_LED") (pin "C") (pinfunction "C_C") (pintype "passive"))
      (node (ref "SHARP_RES") (pin "2") (pinfunction "2_2") (pintype "passive"))
    )
    (net (code "123") (name "Net-(XBEE_AD3_LED-PadC)") (class "Default")
      (node (ref "XBEE_AD3_LED") (pin "C") (pinfunction "C_C") (pintype "passive"))
      (node (ref "XBEE_RES1") (pin "2") (pinfunction "2_2") (pintype "passive"))
    )
    (net (code "124") (name "Net-(XBEE_AD5_LED-PadC)") (class "Default")
      (node (ref "XBEE_AD5_LED") (pin "C") (pinfunction "C_C") (pintype "passive"))
      (node (ref "XBEE_RES2") (pin "2") (pinfunction "2_2") (pintype "passive"))
    )
    (net (code "125") (name "Net-(XBEE_LED4-PadC)") (class "Default")
      (node (ref "XBEE_LED4") (pin "C") (pinfunction "C_C") (pintype "passive"))
      (node (ref "XBEE_RES4") (pin "2") (pinfunction "2_2") (pintype "passive"))
    )
    (net (code "126") (name "Net-(XBEE_ON/SLEEP-PadC)") (class "Default")
      (node (ref "XBEE_ON/SLEEP") (pin "C") (pinfunction "C_C") (pintype "passive"))
      (node (ref "XBEE_RES3") (pin "2") (pinfunction "2_2") (pintype "passive"))
    )
    (net (code "127") (name "unconnected-(FT232_USB_TYPEC-3V3OUT-Pad17)") (class "Default")
      (node (ref "FT232_USB_TYPEC") (pin "17") (pinfunction "3V3OUT_17") (pintype "output"))
    )
    (net (code "128") (name "unconnected-(FT232_USB_TYPEC-CBUS2-Pad13)") (class "Default")
      (node (ref "FT232_USB_TYPEC") (pin "13") (pinfunction "CBUS2_13") (pintype "bidirectional"))
    )
    (net (code "129") (name "unconnected-(FT232_USB_TYPEC-CBUS3-Pad14)") (class "Default")
      (node (ref "FT232_USB_TYPEC") (pin "14") (pinfunction "CBUS3_14") (pintype "bidirectional"))
    )
    (net (code "130") (name "unconnected-(FT232_USB_TYPEC-CBUS4-Pad12)") (class "Default")
      (node (ref "FT232_USB_TYPEC") (pin "12") (pinfunction "CBUS4_12") (pintype "bidirectional"))
    )
    (net (code "131") (name "unconnected-(FT232_USB_TYPEC-OSCI-Pad27)") (class "Default")
      (node (ref "FT232_USB_TYPEC") (pin "27") (pinfunction "OSCI_27") (pintype "input"))
    )
    (net (code "132") (name "unconnected-(FT232_USB_TYPEC-OSCO-Pad28)") (class "Default")
      (node (ref "FT232_USB_TYPEC") (pin "28") (pinfunction "OSCO_28") (pintype "output"))
    )
    (net (code "133") (name "unconnected-(FT232_USB_TYPEC-~{CTS}-Pad11)") (class "Default")
      (node (ref "FT232_USB_TYPEC") (pin "11") (pinfunction "~{CTS}_11") (pintype "input"))
    )
    (net (code "134") (name "unconnected-(FT232_USB_TYPEC-~{DCD}-Pad10)") (class "Default")
      (node (ref "FT232_USB_TYPEC") (pin "10") (pinfunction "~{DCD}_10") (pintype "input"))
    )
    (net (code "135") (name "unconnected-(FT232_USB_TYPEC-~{DSR}-Pad9)") (class "Default")
      (node (ref "FT232_USB_TYPEC") (pin "9") (pinfunction "~{DSR}_9") (pintype "input"))
    )
    (net (code "136") (name "unconnected-(FT232_USB_TYPEC-~{DTR}-Pad2)") (class "Default")
      (node (ref "FT232_USB_TYPEC") (pin "2") (pinfunction "~{DTR}_2") (pintype "output"))
    )
    (net (code "137") (name "unconnected-(FT232_USB_TYPEC-~{RESET}-Pad19)") (class "Default")
      (node (ref "FT232_USB_TYPEC") (pin "19") (pinfunction "~{RESET}_19") (pintype "input"))
    )
    (net (code "138") (name "unconnected-(FT232_USB_TYPEC-~{RI}-Pad6)") (class "Default")
      (node (ref "FT232_USB_TYPEC") (pin "6") (pinfunction "~{RI}_6") (pintype "input"))
    )
    (net (code "139") (name "unconnected-(FT232_USB_TYPEC-~{RTS}-Pad3)") (class "Default")
      (node (ref "FT232_USB_TYPEC") (pin "3") (pinfunction "~{RTS}_3") (pintype "output"))
    )
    (net (code "140") (name "unconnected-(ISPD-S-Pad3)") (class "Default")
      (node (ref "ISP") (pin "3") (pinfunction "S_3") (pintype "passive"))
    )
    (net (code "141") (name "unconnected-(LCD_16*4-DB0-Pad7)") (class "Default")
      (node (ref "LCD_16*4") (pin "7") (pinfunction "DB0_7") (pintype "bidirectional"))
    )
    (net (code "142") (name "unconnected-(LCD_16*4-DB1-Pad8)") (class "Default")
      (node (ref "LCD_16*4") (pin "8") (pinfunction "DB1_8") (pintype "bidirectional"))
    )
    (net (code "143") (name "unconnected-(LCD_16*4-DB2-Pad9)") (class "Default")
      (node (ref "LCD_16*4") (pin "9") (pinfunction "DB2_9") (pintype "bidirectional"))
    )
    (net (code "144") (name "unconnected-(LCD_16*4-DB3-Pad10)") (class "Default")
      (node (ref "LCD_16*4") (pin "10") (pinfunction "DB3_10") (pintype "bidirectional"))
    )
    (net (code "145") (name "unconnected-(MPU_ACC_GYRO-Pad5)") (class "Default")
      (node (ref "MPU_ACC_GYRO") (pin "5") (pinfunction "5_5") (pintype "passive"))
    )
    (net (code "146") (name "unconnected-(MPU_ACC_GYRO-Pad6)") (class "Default")
      (node (ref "MPU_ACC_GYRO") (pin "6") (pinfunction "6_6") (pintype "passive"))
    )
    (net (code "147") (name "unconnected-(MPU_ACC_GYRO-Pad7)") (class "Default")
      (node (ref "MPU_ACC_GYRO") (pin "7") (pinfunction "7_7") (pintype "passive"))
    )
    (net (code "148") (name "unconnected-(S1-P1-Pad4)") (class "Default")
      (node (ref "S1") (pin "4") (pinfunction "P1_4") (pintype "passive"))
    )
    (net (code "149") (name "unconnected-(S1-S1-Pad2)") (class "Default")
      (node (ref "S1") (pin "2") (pinfunction "S1_2") (pintype "passive"))
    )
    (net (code "150") (name "unconnected-(S3-P1-Pad4)") (class "Default")
      (node (ref "S3") (pin "4") (pinfunction "P1_4") (pintype "passive"))
    )
    (net (code "151") (name "unconnected-(S3-S1-Pad2)") (class "Default")
      (node (ref "S3") (pin "2") (pinfunction "S1_2") (pintype "passive"))
    )
    (net (code "152") (name "unconnected-(TSOP_FEMALE-Pad3)") (class "Default")
      (node (ref "TSOP_FEMALE") (pin "3") (pinfunction "3_3") (pintype "passive"))
    )
    (net (code "153") (name "unconnected-(WHITE_LINEB-S-Pad10)") (class "Default")
      (node (ref "WHITE_LINE") (pin "10") (pinfunction "S_10") (pintype "passive"))
    )
    (net (code "154") (name "unconnected-(WHITE_LINEG-S-Pad6)") (class "Default")
      (node (ref "WHITE_LINE") (pin "6") (pinfunction "S_6") (pintype "passive"))
    )
    (net (code "155") (name "unconnected-(WHITE_LINEI-S-Pad8)") (class "Default")
      (node (ref "WHITE_LINE") (pin "8") (pinfunction "S_8") (pintype "passive"))
    )
    (net (code "156") (name "unconnected-(XBEE-AD0{slash}DIO0-Pad20)") (class "Default")
      (node (ref "XBEE") (pin "20") (pinfunction "AD0/DIO0_20") (pintype "bidirectional"))
    )
    (net (code "157") (name "unconnected-(XBEE-AD1{slash}DIO1-Pad19)") (class "Default")
      (node (ref "XBEE") (pin "19") (pinfunction "AD1/DIO1_19") (pintype "bidirectional"))
    )
    (net (code "158") (name "unconnected-(XBEE-AD2{slash}DIO2-Pad18)") (class "Default")
      (node (ref "XBEE") (pin "18") (pinfunction "AD2/DIO2_18") (pintype "bidirectional"))
    )
    (net (code "159") (name "unconnected-(XBEE-AD4{slash}DIO4-Pad11)") (class "Default")
      (node (ref "XBEE") (pin "11") (pinfunction "AD4/DIO4_11") (pintype "bidirectional"))
    )
    (net (code "160") (name "unconnected-(XBEE-CTS{slash}DIO7-Pad12)") (class "Default")
      (node (ref "XBEE") (pin "12") (pinfunction "CTS/DIO7_12") (pintype "bidirectional"))
    )
    (net (code "161") (name "unconnected-(XBEE-DO8-Pad4)") (class "Default")
      (node (ref "XBEE") (pin "4") (pinfunction "DO8_4") (pintype "output"))
    )
    (net (code "162") (name "unconnected-(XBEE-DTR{slash}DI8-Pad9)") (class "Default")
      (node (ref "XBEE") (pin "9") (pinfunction "DTR/DI8_9") (pintype "input"))
    )
    (net (code "163") (name "unconnected-(XBEE-PWM1-Pad7)") (class "Default")
      (node (ref "XBEE") (pin "7") (pinfunction "PWM1_7") (pintype "output"))
    )
    (net (code "164") (name "unconnected-(XBEE-RESERVED-Pad8)") (class "Default")
      (node (ref "XBEE") (pin "8") (pinfunction "RESERVED_8") (pintype "no_connect"))
    )
    (net (code "165") (name "unconnected-(XBEE-RESET-Pad5)") (class "Default")
      (node (ref "XBEE") (pin "5") (pinfunction "RESET_5") (pintype "input"))
    )
    (net (code "166") (name "unconnected-(XBEE-RTS{slash}AD6{slash}DIO6-Pad16)") (class "Default")
      (node (ref "XBEE") (pin "16") (pinfunction "RTS/AD6/DIO6_16") (pintype "bidirectional"))
    )
    (net (code "167") (name "unconnected-(XBEE-VREF-Pad14)") (class "Default")
      (node (ref "XBEE") (pin "14") (pinfunction "VREF_14") (pintype "input"))
    )
  )
)
